# TEC_controller_v1_0.net
KiCad netlist of a schematic drawn in EAGLE
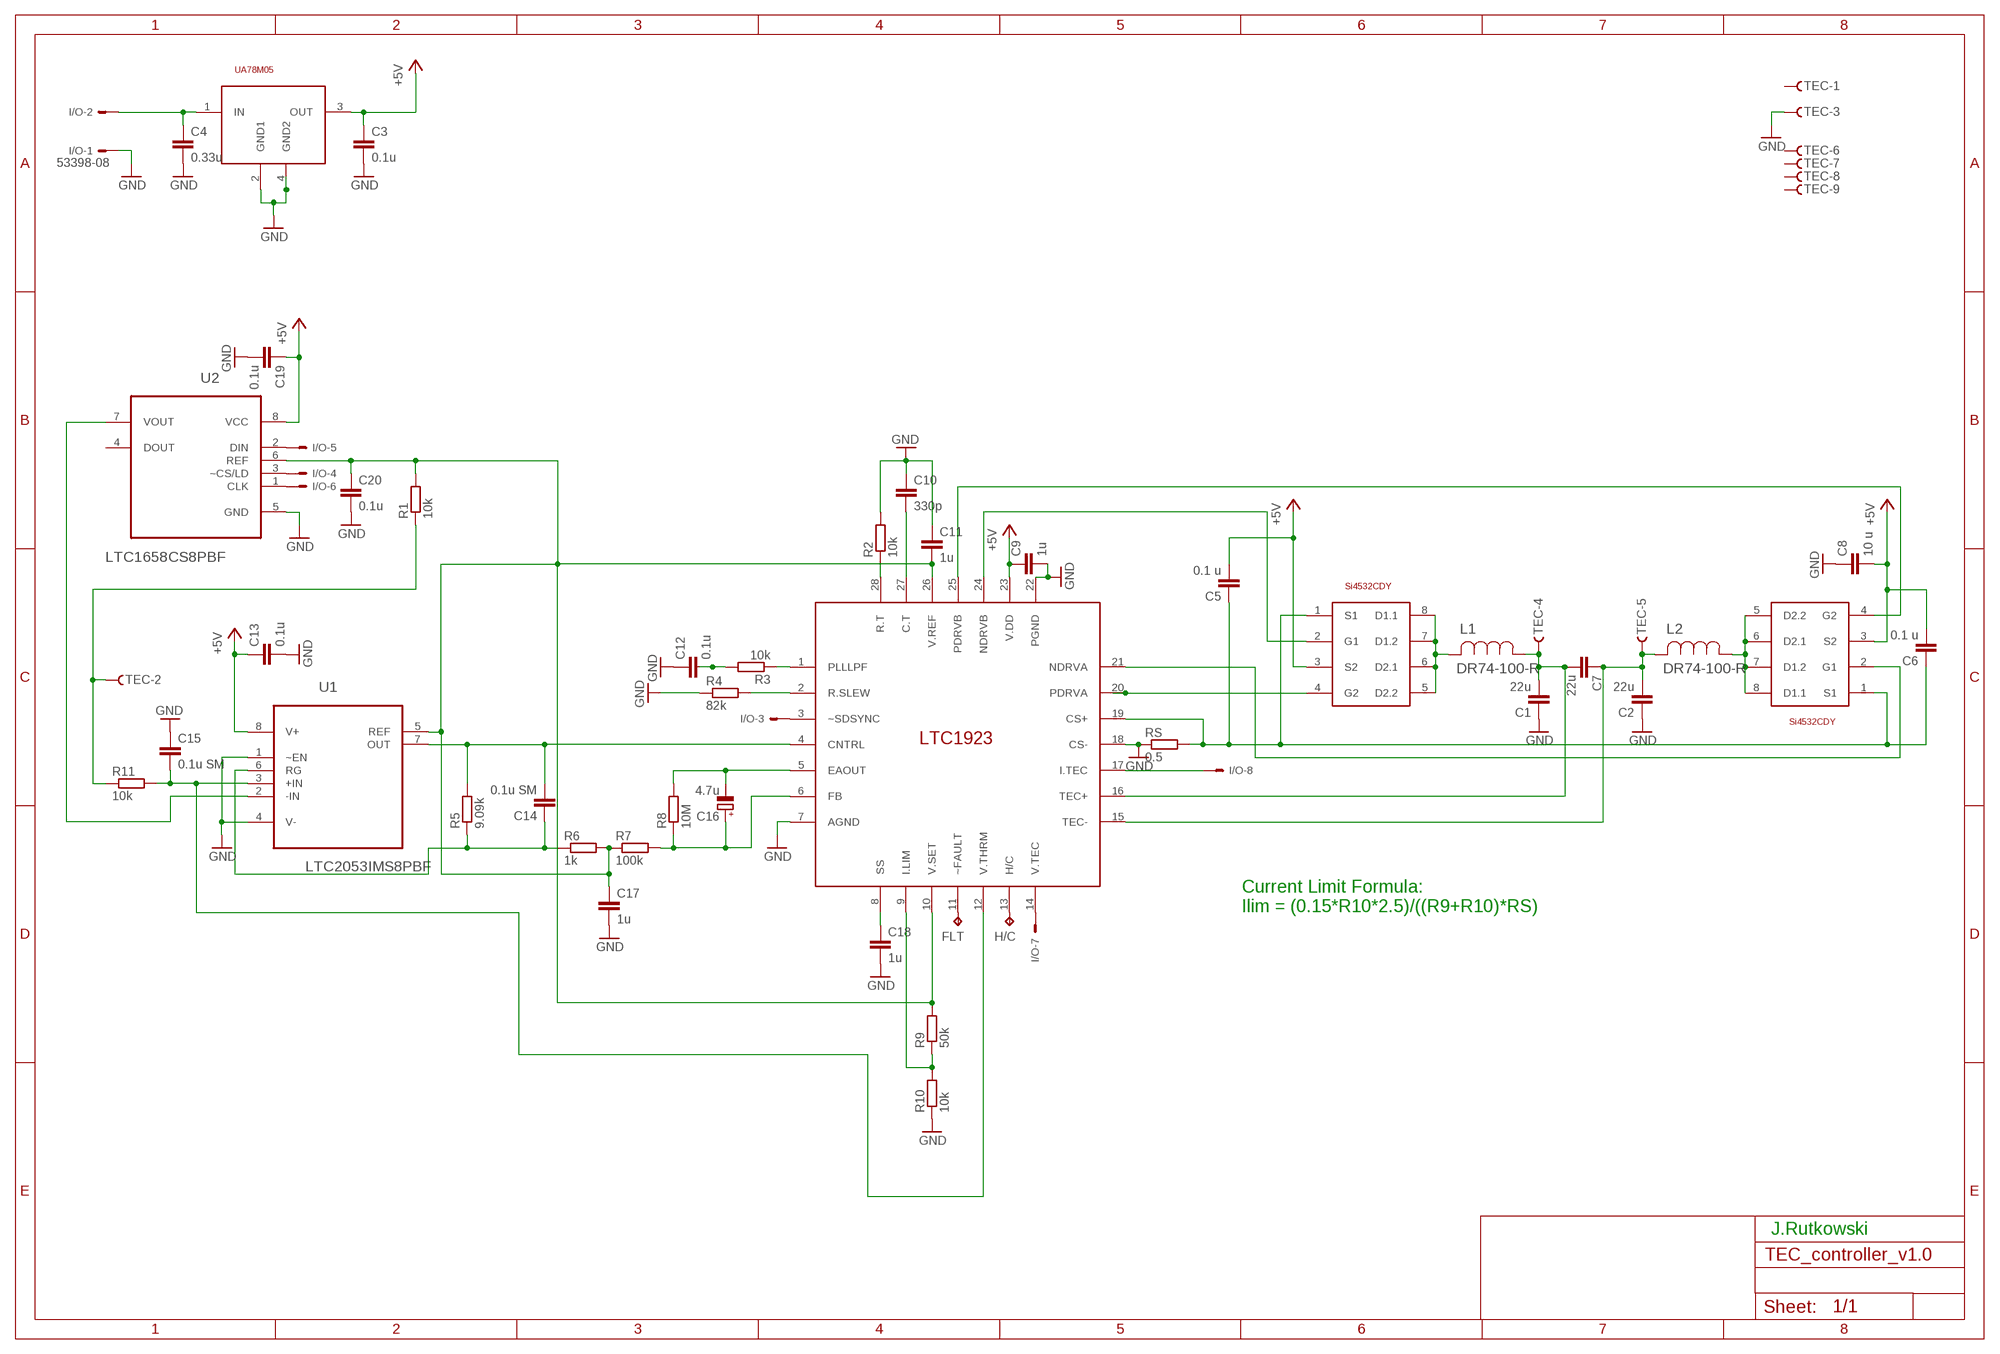
[diagram p0: schematic, sheet 1]

(export (version "E")
  (design (tool "Eeschema 10.0.6"))
  (components
    (comp (ref "C1")
      (value "22u")
      (footprint "eagle-import:C1210K")
      (libsource (lib "eagle-import") (part "C-EUC1210K"))
    )
    (comp (ref "C2")
      (value "22u")
      (footprint "eagle-import:C1210K")
      (libsource (lib "eagle-import") (part "C-EUC1210K"))
    )
    (comp (ref "C3")
      (value "0.1u")
      (footprint "eagle-import:C0805K")
      (libsource (lib "eagle-import") (part "C-EUC0805K"))
    )
    (comp (ref "C4")
      (value "0.33u")
      (footprint "eagle-import:C0805K")
      (libsource (lib "eagle-import") (part "C-EUC0805K"))
    )
    (comp (ref "C5")
      (value "0.1 u")
      (footprint "eagle-import:C0805K")
      (libsource (lib "eagle-import") (part "C-EUC0805K"))
    )
    (comp (ref "C6")
      (value "0.1 u")
      (footprint "eagle-import:C0805K")
      (libsource (lib "eagle-import") (part "C-EUC0805K"))
    )
    (comp (ref "C7")
      (value "22u")
      (footprint "eagle-import:C1210K")
      (libsource (lib "eagle-import") (part "C-EUC1210K"))
    )
    (comp (ref "C8")
      (value "10 u")
      (footprint "eagle-import:C1206K")
      (libsource (lib "eagle-import") (part "C-EUC1206K"))
    )
    (comp (ref "C9")
      (value "1u")
      (footprint "eagle-import:C0603K")
      (libsource (lib "eagle-import") (part "C-EUC0603K"))
    )
    (comp (ref "C10")
      (value "330p")
      (footprint "eagle-import:C0603K")
      (libsource (lib "eagle-import") (part "C-EUC0603K"))
    )
    (comp (ref "C11")
      (value "1u")
      (footprint "eagle-import:C0603K")
      (libsource (lib "eagle-import") (part "C-EUC0603K"))
    )
    (comp (ref "C12")
      (value "0.1u")
      (footprint "eagle-import:C0603K")
      (libsource (lib "eagle-import") (part "C-EUC0603K"))
    )
    (comp (ref "C13")
      (value "0.1u")
      (footprint "eagle-import:C0603")
      (libsource (lib "eagle-import") (part "C-EUC0603"))
    )
    (comp (ref "C14")
      (value "0.1u SM")
      (footprint "eagle-import:C1210")
      (libsource (lib "eagle-import") (part "C-EUC1210"))
    )
    (comp (ref "C15")
      (value "0.1u SM")
      (footprint "eagle-import:C1210")
      (libsource (lib "eagle-import") (part "C-EUC1210"))
    )
    (comp (ref "C16")
      (value "4.7u")
      (footprint "eagle-import:A_3216-18W")
      (libsource (lib "eagle-import") (part "CPOL-EUA/3216-18W"))
    )
    (comp (ref "C17")
      (value "1u")
      (footprint "eagle-import:C0603K")
      (libsource (lib "eagle-import") (part "C-EUC0603K"))
    )
    (comp (ref "C18")
      (value "1u")
      (footprint "eagle-import:C0603K")
      (libsource (lib "eagle-import") (part "C-EUC0603K"))
    )
    (comp (ref "C19")
      (value "0.1u")
      (footprint "eagle-import:C0603K")
      (libsource (lib "eagle-import") (part "C-EUC0603K"))
    )
    (comp (ref "C20")
      (value "0.1u")
      (footprint "eagle-import:C0603K")
      (libsource (lib "eagle-import") (part "C-EUC0603K"))
    )
    (comp (ref "FLT")
      (value "TPTP17SQ")
      (footprint "eagle-import:TP17SQ")
      (libsource (lib "eagle-import") (part "TPTP17SQ"))
    )
    (comp (ref "H/C")
      (value "TPTP17SQ")
      (footprint "eagle-import:TP17SQ")
      (libsource (lib "eagle-import") (part "TPTP17SQ"))
    )
    (comp (ref "I/O")
      (value "53398-08")
      (footprint "eagle-import:53398-08")
      (libsource (lib "eagle-import") (part "53?-08398"))
    )
    (comp (ref "L1")
      (value "DR74-100-R")
      (footprint "eagle-import:INDM7676X435N")
      (fields (field (name "TOLERANCE") "20%"))
      (libsource (lib "eagle-import") (part "DR74-100-R"))
    )
    (comp (ref "L2")
      (value "DR74-100-R")
      (footprint "eagle-import:INDM7676X435N")
      (fields (field (name "TOLERANCE") "20%"))
      (libsource (lib "eagle-import") (part "DR74-100-R"))
    )
    (comp (ref "R1")
      (value "10k")
      (footprint "eagle-import:R0603")
      (libsource (lib "eagle-import") (part "R-EU_R0603"))
    )
    (comp (ref "R2")
      (value "10k")
      (footprint "eagle-import:R0603")
      (libsource (lib "eagle-import") (part "R-EU_R0603"))
    )
    (comp (ref "R3")
      (value "10k")
      (footprint "eagle-import:R0603")
      (libsource (lib "eagle-import") (part "R-EU_R0603"))
    )
    (comp (ref "R4")
      (value "82k")
      (footprint "eagle-import:R0603")
      (libsource (lib "eagle-import") (part "R-EU_R0603"))
    )
    (comp (ref "R5")
      (value "9.09k")
      (footprint "eagle-import:R0603")
      (libsource (lib "eagle-import") (part "R-EU_R0603"))
    )
    (comp (ref "R6")
      (value "1k")
      (footprint "eagle-import:R0603")
      (libsource (lib "eagle-import") (part "R-EU_R0603"))
    )
    (comp (ref "R7")
      (value "100k")
      (footprint "eagle-import:R0603")
      (libsource (lib "eagle-import") (part "R-EU_R0603"))
    )
    (comp (ref "R8")
      (value "10M")
      (footprint "eagle-import:R0603")
      (libsource (lib "eagle-import") (part "R-EU_R0603"))
    )
    (comp (ref "R9")
      (value "50k")
      (footprint "eagle-import:R0603")
      (libsource (lib "eagle-import") (part "R-EU_R0603"))
    )
    (comp (ref "R10")
      (value "10k")
      (footprint "eagle-import:R0603")
      (libsource (lib "eagle-import") (part "R-EU_R0603"))
    )
    (comp (ref "R11")
      (value "10k")
      (footprint "eagle-import:R0603")
      (libsource (lib "eagle-import") (part "R-EU_R0603"))
    )
    (comp (ref "RS")
      (value "0.5")
      (footprint "eagle-import:R1206")
      (libsource (lib "eagle-import") (part "R-EU_R1206"))
    )
    (comp (ref "TEC")
      (value "F09HPS")
      (footprint "eagle-import:F09HP")
      (libsource (lib "eagle-import") (part "F09?SHP"))
    )
    (comp (ref "U$1")
      (value "LTC1923")
      (footprint "eagle-import:SSOP28")
      (fields (field (name "MPN") "LTC1923EGN#PBF"))
      (libsource (lib "eagle-import") (part "LTC1923"))
    )
    (comp (ref "U$2")
      (value "SI4532CDY")
      (footprint "eagle-import:SOIC127P600X175-8N")
      (fields (field (name "MPN") "SI4532CDY-T1-GE3"))
      (libsource (lib "eagle-import") (part "SI4532CDY"))
    )
    (comp (ref "U$3")
      (value "SI4532CDY")
      (footprint "eagle-import:SOIC127P600X175-8N")
      (fields (field (name "MPN") "SI4532CDY-T1-GE3"))
      (libsource (lib "eagle-import") (part "SI4532CDY"))
    )
    (comp (ref "U$6")
      (value "UA78M05")
      (footprint "eagle-import:SOT-223")
      (libsource (lib "eagle-import") (part "UA78M05"))
    )
    (comp (ref "U1")
      (value "LTC2053IMS8PBF")
      (footprint "eagle-import:SOP65P490X110-8N")
      (fields (field (name "MPN") "LTC2053IMS8#PBF"))
      (libsource (lib "eagle-import") (part "LTC2053IMS8PBF"))
    )
    (comp (ref "U2")
      (value "LTC1658CS8PBF")
      (footprint "eagle-import:SOIC127P600X175-8N")
      (fields (field (name "MPN") "LTC1658CS8#PBF"))
      (libsource (lib "eagle-import") (part "LTC1658CS8PBF"))
    )
  )
  (nets
    (net (code "1") (name "+5V") (class "Default")
      (node (ref "C13") (pin "1") (pinfunction "1_1") (pintype "passive"))
      (node (ref "C19") (pin "1") (pinfunction "1_1") (pintype "passive"))
      (node (ref "C3") (pin "1") (pinfunction "1_1") (pintype "passive"))
      (node (ref "C5") (pin "2") (pinfunction "2_2") (pintype "passive"))
      (node (ref "C6") (pin "2") (pinfunction "2_2") (pintype "passive"))
      (node (ref "C8") (pin "2") (pinfunction "2_2") (pintype "passive"))
      (node (ref "C9") (pin "1") (pinfunction "1_1") (pintype "passive"))
      (node (ref "U$1") (pin "23") (pinfunction "V.DD_23") (pintype "bidirectional"))
      (node (ref "U$2") (pin "3") (pinfunction "S2_3") (pintype "bidirectional"))
      (node (ref "U$3") (pin "3") (pinfunction "S2_3") (pintype "bidirectional"))
      (node (ref "U$6") (pin "3") (pinfunction "OUT_3") (pintype "bidirectional"))
      (node (ref "U1") (pin "8") (pinfunction "V+_8") (pintype "power_in"))
      (node (ref "U2") (pin "8") (pinfunction "VCC_8") (pintype "power_in"))
    )
    (net (code "2") (name "GND") (class "Default")
      (node (ref "C1") (pin "1") (pinfunction "1_1") (pintype "passive"))
      (node (ref "C10") (pin "1") (pinfunction "1_1") (pintype "passive"))
      (node (ref "C11") (pin "1") (pinfunction "1_1") (pintype "passive"))
      (node (ref "C12") (pin "1") (pinfunction "1_1") (pintype "passive"))
      (node (ref "C13") (pin "2") (pinfunction "2_2") (pintype "passive"))
      (node (ref "C15") (pin "1") (pinfunction "1_1") (pintype "passive"))
      (node (ref "C17") (pin "2") (pinfunction "2_2") (pintype "passive"))
      (node (ref "C18") (pin "2") (pinfunction "2_2") (pintype "passive"))
      (node (ref "C19") (pin "2") (pinfunction "2_2") (pintype "passive"))
      (node (ref "C2") (pin "1") (pinfunction "1_1") (pintype "passive"))
      (node (ref "C20") (pin "2") (pinfunction "2_2") (pintype "passive"))
      (node (ref "C3") (pin "2") (pinfunction "2_2") (pintype "passive"))
      (node (ref "C4") (pin "2") (pinfunction "2_2") (pintype "passive"))
      (node (ref "C8") (pin "1") (pinfunction "1_1") (pintype "passive"))
      (node (ref "C9") (pin "2") (pinfunction "2_2") (pintype "passive"))
      (node (ref "I/O") (pin "1") (pinfunction "S_1") (pintype "passive"))
      (node (ref "R10") (pin "1") (pinfunction "1_1") (pintype "passive"))
      (node (ref "R2") (pin "2") (pinfunction "2_2") (pintype "passive"))
      (node (ref "R4") (pin "1") (pinfunction "1_1") (pintype "passive"))
      (node (ref "RS") (pin "1") (pinfunction "1_1") (pintype "passive"))
      (node (ref "TEC") (pin "3") (pinfunction "F_3") (pintype "passive"))
      (node (ref "U$1") (pin "18") (pinfunction "CS-_18") (pintype "bidirectional"))
      (node (ref "U$1") (pin "22") (pinfunction "PGND_22") (pintype "bidirectional"))
      (node (ref "U$1") (pin "7") (pinfunction "AGND_7") (pintype "bidirectional"))
      (node (ref "U$6") (pin "2") (pinfunction "GND1_2") (pintype "bidirectional"))
      (node (ref "U$6") (pin "4") (pinfunction "GND2_4") (pintype "bidirectional"))
      (node (ref "U1") (pin "1") (pinfunction "~{EN}_1") (pintype "input"))
      (node (ref "U1") (pin "4") (pinfunction "V-_4") (pintype "power_in"))
      (node (ref "U2") (pin "5") (pinfunction "GND_5") (pintype "passive"))
    )
    (net (code "3") (name "Net-(C12-Pad2)") (class "Default")
      (node (ref "C12") (pin "2") (pinfunction "2_2") (pintype "passive"))
      (node (ref "R3") (pin "2") (pinfunction "2_2") (pintype "passive"))
    )
    (net (code "4") (name "Net-(I/OB-S)") (class "Default")
      (node (ref "C4") (pin "1") (pinfunction "1_1") (pintype "passive"))
      (node (ref "I/O") (pin "2") (pinfunction "S_2") (pintype "passive"))
      (node (ref "U$6") (pin "1") (pinfunction "IN_1") (pintype "bidirectional"))
    )
    (net (code "5") (name "Net-(I/OC-S)") (class "Default")
      (node (ref "I/O") (pin "3") (pinfunction "S_3") (pintype "passive"))
      (node (ref "U$1") (pin "3") (pinfunction "~{SDSYNC}_3") (pintype "bidirectional"))
    )
    (net (code "6") (name "Net-(I/OD-S)") (class "Default")
      (node (ref "I/O") (pin "4") (pinfunction "S_4") (pintype "passive"))
      (node (ref "U2") (pin "3") (pinfunction "~{CS/LD}_3") (pintype "input"))
    )
    (net (code "7") (name "Net-(I/OE-S)") (class "Default")
      (node (ref "I/O") (pin "5") (pinfunction "S_5") (pintype "passive"))
      (node (ref "U2") (pin "2") (pinfunction "DIN_2") (pintype "input"))
    )
    (net (code "8") (name "Net-(I/OF-S)") (class "Default")
      (node (ref "I/O") (pin "6") (pinfunction "S_6") (pintype "passive"))
      (node (ref "U2") (pin "1") (pinfunction "CLK_1") (pintype "input"))
    )
    (net (code "9") (name "Net-(I/OG-S)") (class "Default")
      (node (ref "I/O") (pin "7") (pinfunction "S_7") (pintype "passive"))
      (node (ref "U$1") (pin "14") (pinfunction "V.TEC_14") (pintype "bidirectional"))
    )
    (net (code "10") (name "Net-(I/OH-S)") (class "Default")
      (node (ref "I/O") (pin "8") (pinfunction "S_8") (pintype "passive"))
      (node (ref "U$1") (pin "17") (pinfunction "I.TEC_17") (pintype "bidirectional"))
    )
    (net (code "11") (name "Net-(TECB-F)") (class "Default")
      (node (ref "R1") (pin "1") (pinfunction "1_1") (pintype "passive"))
      (node (ref "R11") (pin "1") (pinfunction "1_1") (pintype "passive"))
      (node (ref "TEC") (pin "2") (pinfunction "F_2") (pintype "passive"))
    )
    (net (code "12") (name "Net-(TECD-F)") (class "Default")
      (node (ref "C1") (pin "2") (pinfunction "2_2") (pintype "passive"))
      (node (ref "C7") (pin "2") (pinfunction "2_2") (pintype "passive"))
      (node (ref "L1") (pin "1") (pinfunction "1_1") (pintype "passive"))
      (node (ref "TEC") (pin "4") (pinfunction "F_4") (pintype "passive"))
      (node (ref "U$1") (pin "16") (pinfunction "TEC+_16") (pintype "bidirectional"))
    )
    (net (code "13") (name "Net-(TECE-F)") (class "Default")
      (node (ref "C2") (pin "2") (pinfunction "2_2") (pintype "passive"))
      (node (ref "C7") (pin "1") (pinfunction "1_1") (pintype "passive"))
      (node (ref "L2") (pin "2") (pinfunction "2_2") (pintype "passive"))
      (node (ref "TEC") (pin "5") (pinfunction "F_5") (pintype "passive"))
      (node (ref "U$1") (pin "15") (pinfunction "TEC-_15") (pintype "bidirectional"))
    )
    (net (code "14") (name "Net-(U$1-C.T)") (class "Default")
      (node (ref "C10") (pin "2") (pinfunction "2_2") (pintype "passive"))
      (node (ref "U$1") (pin "27") (pinfunction "C.T_27") (pintype "bidirectional"))
    )
    (net (code "15") (name "Net-(U$1-CNTRL)") (class "Default")
      (node (ref "C14") (pin "2") (pinfunction "2_2") (pintype "passive"))
      (node (ref "R5") (pin "2") (pinfunction "2_2") (pintype "passive"))
      (node (ref "U$1") (pin "4") (pinfunction "CNTRL_4") (pintype "bidirectional"))
      (node (ref "U1") (pin "7") (pinfunction "OUT_7") (pintype "output"))
    )
    (net (code "16") (name "Net-(U$1-CS+)") (class "Default")
      (node (ref "C5") (pin "1") (pinfunction "1_1") (pintype "passive"))
      (node (ref "C6") (pin "1") (pinfunction "1_1") (pintype "passive"))
      (node (ref "RS") (pin "2") (pinfunction "2_2") (pintype "passive"))
      (node (ref "U$1") (pin "19") (pinfunction "CS+_19") (pintype "bidirectional"))
      (node (ref "U$2") (pin "1") (pinfunction "S1_1") (pintype "bidirectional"))
      (node (ref "U$3") (pin "1") (pinfunction "S1_1") (pintype "bidirectional"))
    )
    (net (code "17") (name "Net-(U$1-EAOUT)") (class "Default")
      (node (ref "C16") (pin "-") (pinfunction "-_-") (pintype "passive"))
      (node (ref "R8") (pin "2") (pinfunction "2_2") (pintype "passive"))
      (node (ref "U$1") (pin "5") (pinfunction "EAOUT_5") (pintype "bidirectional"))
    )
    (net (code "18") (name "Net-(U$1-FB)") (class "Default")
      (node (ref "C16") (pin "+") (pinfunction "+_+") (pintype "passive"))
      (node (ref "R7") (pin "2") (pinfunction "2_2") (pintype "passive"))
      (node (ref "R8") (pin "1") (pinfunction "1_1") (pintype "passive"))
      (node (ref "U$1") (pin "6") (pinfunction "FB_6") (pintype "bidirectional"))
    )
    (net (code "19") (name "Net-(U$1-H{slash}C)") (class "Default")
      (node (ref "H/C") (pin "TP") (pinfunction "TP_TP") (pintype "input"))
      (node (ref "U$1") (pin "13") (pinfunction "H/C_13") (pintype "bidirectional"))
    )
    (net (code "20") (name "Net-(U$1-I.LIM)") (class "Default")
      (node (ref "R10") (pin "2") (pinfunction "2_2") (pintype "passive"))
      (node (ref "R9") (pin "1") (pinfunction "1_1") (pintype "passive"))
      (node (ref "U$1") (pin "9") (pinfunction "I.LIM_9") (pintype "bidirectional"))
    )
    (net (code "21") (name "Net-(U$1-NDRVA)") (class "Default")
      (node (ref "U$1") (pin "21") (pinfunction "NDRVA_21") (pintype "bidirectional"))
      (node (ref "U$3") (pin "2") (pinfunction "G1_2") (pintype "bidirectional"))
    )
    (net (code "22") (name "Net-(U$1-NDRVB)") (class "Default")
      (node (ref "U$1") (pin "24") (pinfunction "NDRVB_24") (pintype "bidirectional"))
      (node (ref "U$2") (pin "2") (pinfunction "G1_2") (pintype "bidirectional"))
    )
    (net (code "23") (name "Net-(U$1-PDRVA)") (class "Default")
      (node (ref "U$1") (pin "20") (pinfunction "PDRVA_20") (pintype "bidirectional"))
      (node (ref "U$2") (pin "4") (pinfunction "G2_4") (pintype "bidirectional"))
    )
    (net (code "24") (name "Net-(U$1-PDRVB)") (class "Default")
      (node (ref "U$1") (pin "25") (pinfunction "PDRVB_25") (pintype "bidirectional"))
      (node (ref "U$3") (pin "4") (pinfunction "G2_4") (pintype "bidirectional"))
    )
    (net (code "25") (name "Net-(U$1-PLLLPF)") (class "Default")
      (node (ref "R3") (pin "1") (pinfunction "1_1") (pintype "passive"))
      (node (ref "U$1") (pin "1") (pinfunction "PLLLPF_1") (pintype "bidirectional"))
    )
    (net (code "26") (name "Net-(U$1-R.SLEW)") (class "Default")
      (node (ref "R4") (pin "2") (pinfunction "2_2") (pintype "passive"))
      (node (ref "U$1") (pin "2") (pinfunction "R.SLEW_2") (pintype "bidirectional"))
    )
    (net (code "27") (name "Net-(U$1-R.T)") (class "Default")
      (node (ref "R2") (pin "1") (pinfunction "1_1") (pintype "passive"))
      (node (ref "U$1") (pin "28") (pinfunction "R.T_28") (pintype "bidirectional"))
    )
    (net (code "28") (name "Net-(U$1-SS)") (class "Default")
      (node (ref "C18") (pin "1") (pinfunction "1_1") (pintype "passive"))
      (node (ref "U$1") (pin "8") (pinfunction "SS_8") (pintype "bidirectional"))
    )
    (net (code "29") (name "Net-(U$1-V.REF)") (class "Default")
      (node (ref "C11") (pin "2") (pinfunction "2_2") (pintype "passive"))
      (node (ref "C17") (pin "1") (pinfunction "1_1") (pintype "passive"))
      (node (ref "C20") (pin "1") (pinfunction "1_1") (pintype "passive"))
      (node (ref "R1") (pin "2") (pinfunction "2_2") (pintype "passive"))
      (node (ref "R6") (pin "2") (pinfunction "2_2") (pintype "passive"))
      (node (ref "R7") (pin "1") (pinfunction "1_1") (pintype "passive"))
      (node (ref "R9") (pin "2") (pinfunction "2_2") (pintype "passive"))
      (node (ref "U$1") (pin "10") (pinfunction "V.SET_10") (pintype "bidirectional"))
      (node (ref "U$1") (pin "26") (pinfunction "V.REF_26") (pintype "bidirectional"))
      (node (ref "U1") (pin "5") (pinfunction "REF_5") (pintype "output"))
      (node (ref "U2") (pin "6") (pinfunction "REF_6") (pintype "input"))
    )
    (net (code "30") (name "Net-(U$1-V.THRM)") (class "Default")
      (node (ref "C15") (pin "2") (pinfunction "2_2") (pintype "passive"))
      (node (ref "R11") (pin "2") (pinfunction "2_2") (pintype "passive"))
      (node (ref "U$1") (pin "12") (pinfunction "V.THRM_12") (pintype "bidirectional"))
      (node (ref "U1") (pin "3") (pinfunction "+IN_3") (pintype "input"))
    )
    (net (code "31") (name "Net-(U$1-~{FAULT})") (class "Default")
      (node (ref "FLT") (pin "TP") (pinfunction "TP_TP") (pintype "input"))
      (node (ref "U$1") (pin "11") (pinfunction "~{FAULT}_11") (pintype "bidirectional"))
    )
    (net (code "32") (name "Net-(U$2-D1.1)") (class "Default")
      (node (ref "L1") (pin "2") (pinfunction "2_2") (pintype "passive"))
      (node (ref "U$2") (pin "5") (pinfunction "D2.2_5") (pintype "bidirectional"))
      (node (ref "U$2") (pin "6") (pinfunction "D2.1_6") (pintype "bidirectional"))
      (node (ref "U$2") (pin "7") (pinfunction "D1.2_7") (pintype "bidirectional"))
      (node (ref "U$2") (pin "8") (pinfunction "D1.1_8") (pintype "bidirectional"))
    )
    (net (code "33") (name "Net-(U$3-D1.1)") (class "Default")
      (node (ref "L2") (pin "1") (pinfunction "1_1") (pintype "passive"))
      (node (ref "U$3") (pin "5") (pinfunction "D2.2_5") (pintype "bidirectional"))
      (node (ref "U$3") (pin "6") (pinfunction "D2.1_6") (pintype "bidirectional"))
      (node (ref "U$3") (pin "7") (pinfunction "D1.2_7") (pintype "bidirectional"))
      (node (ref "U$3") (pin "8") (pinfunction "D1.1_8") (pintype "bidirectional"))
    )
    (net (code "34") (name "Net-(U1--IN)") (class "Default")
      (node (ref "U1") (pin "2") (pinfunction "-IN_2") (pintype "input"))
      (node (ref "U2") (pin "7") (pinfunction "VOUT_7") (pintype "output"))
    )
    (net (code "35") (name "Net-(U1-RG)") (class "Default")
      (node (ref "C14") (pin "1") (pinfunction "1_1") (pintype "passive"))
      (node (ref "R5") (pin "1") (pinfunction "1_1") (pintype "passive"))
      (node (ref "R6") (pin "1") (pinfunction "1_1") (pintype "passive"))
      (node (ref "U1") (pin "6") (pinfunction "RG_6") (pintype "input"))
    )
    (net (code "36") (name "unconnected-(TECA-F-Pad1)") (class "Default")
      (node (ref "TEC") (pin "1") (pinfunction "F_1") (pintype "passive"))
    )
    (net (code "37") (name "unconnected-(TECF-F-Pad6)") (class "Default")
      (node (ref "TEC") (pin "6") (pinfunction "F_6") (pintype "passive"))
    )
    (net (code "38") (name "unconnected-(TECG-F-Pad7)") (class "Default")
      (node (ref "TEC") (pin "7") (pinfunction "F_7") (pintype "passive"))
    )
    (net (code "39") (name "unconnected-(TECH-F-Pad8)") (class "Default")
      (node (ref "TEC") (pin "8") (pinfunction "F_8") (pintype "passive"))
    )
    (net (code "40") (name "unconnected-(TECI-F-Pad9)") (class "Default")
      (node (ref "TEC") (pin "9") (pinfunction "F_9") (pintype "passive"))
    )
    (net (code "41") (name "unconnected-(U2-DOUT-Pad4)") (class "Default")
      (node (ref "U2") (pin "4") (pinfunction "DOUT_4") (pintype "output"))
    )
  )
)
